# WS2812B-compact.net
KiCad netlist of a schematic drawn in EAGLE
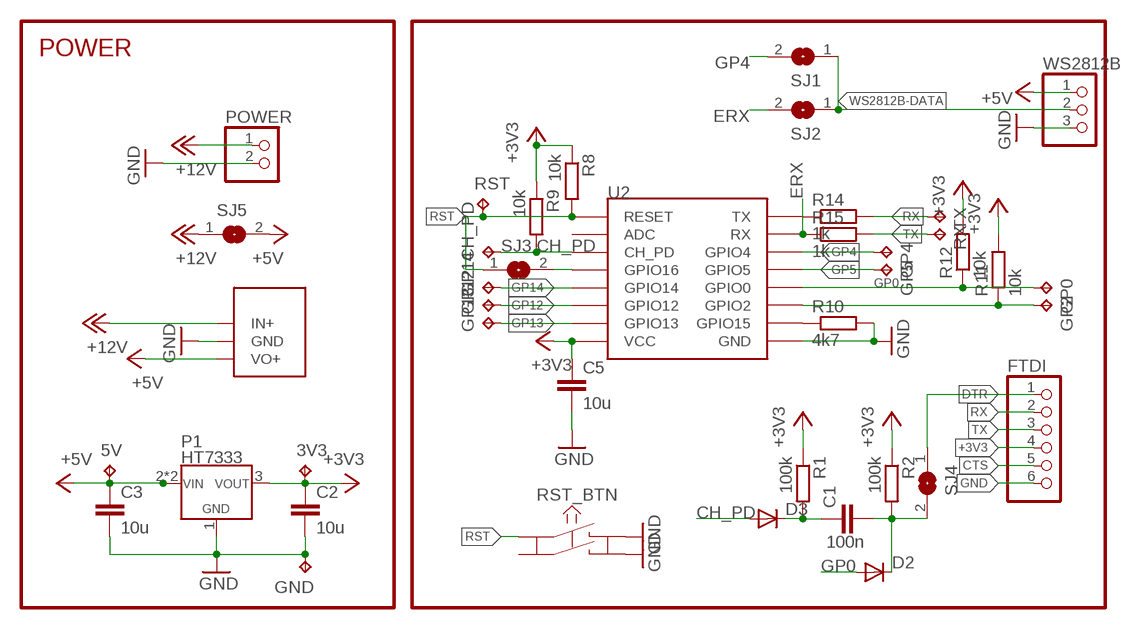
[diagram p0: schematic, sheet 1]

(export (version "E")
  (design (tool "Eeschema 10.0.6"))
  (components
    (comp (ref "3V3")
      (value "TPB2,54")
      (footprint "eagle-import:B2,54")
      (libsource (lib "eagle-import") (part "TPB2,54"))
    )
    (comp (ref "5V")
      (value "TPB2,54")
      (footprint "eagle-import:B2,54")
      (libsource (lib "eagle-import") (part "TPB2,54"))
    )
    (comp (ref "C1")
      (value "100n")
      (footprint "eagle-import:C1206")
      (libsource (lib "eagle-import") (part "C-EUC1206"))
    )
    (comp (ref "C2")
      (value "10u")
      (footprint "eagle-import:C1206")
      (libsource (lib "eagle-import") (part "C-EUC1206"))
    )
    (comp (ref "C3")
      (value "10u")
      (footprint "eagle-import:C1206")
      (libsource (lib "eagle-import") (part "C-EUC1206"))
    )
    (comp (ref "C5")
      (value "10u")
      (footprint "eagle-import:C1206")
      (libsource (lib "eagle-import") (part "C-EUC1206"))
    )
    (comp (ref "CH_PD")
      (value "TPB1,27")
      (footprint "eagle-import:B1,27")
      (libsource (lib "eagle-import") (part "TPB1,27"))
    )
    (comp (ref "D2")
      (value "DIODE-MINIMELF")
      (footprint "eagle-import:MINIMELF")
      (libsource (lib "eagle-import") (part "DIODE-MINIMELF"))
    )
    (comp (ref "D3")
      (value "DIODE-MINIMELF")
      (footprint "eagle-import:MINIMELF")
      (libsource (lib "eagle-import") (part "DIODE-MINIMELF"))
    )
    (comp (ref "FTDI")
      (value "PINHD-1X06_2.54-S")
      (footprint "eagle-import:1X06-S")
      (libsource (lib "eagle-import") (part "PINHD-1X06_2.54-S"))
    )
    (comp (ref "GND")
      (value "TPB2,54")
      (footprint "eagle-import:B2,54")
      (libsource (lib "eagle-import") (part "TPB2,54"))
    )
    (comp (ref "GP0")
      (value "TPB1,27")
      (footprint "eagle-import:B1,27")
      (libsource (lib "eagle-import") (part "TPB1,27"))
    )
    (comp (ref "GP2")
      (value "TPB1,27")
      (footprint "eagle-import:B1,27")
      (libsource (lib "eagle-import") (part "TPB1,27"))
    )
    (comp (ref "GP4")
      (value "TPB1,27")
      (footprint "eagle-import:B1,27")
      (libsource (lib "eagle-import") (part "TPB1,27"))
    )
    (comp (ref "GP5")
      (value "TPB1,27")
      (footprint "eagle-import:B1,27")
      (libsource (lib "eagle-import") (part "TPB1,27"))
    )
    (comp (ref "GP12")
      (value "TPB1,27")
      (footprint "eagle-import:B1,27")
      (libsource (lib "eagle-import") (part "TPB1,27"))
    )
    (comp (ref "GP13")
      (value "TPB1,27")
      (footprint "eagle-import:B1,27")
      (libsource (lib "eagle-import") (part "TPB1,27"))
    )
    (comp (ref "GP14")
      (value "TPB1,27")
      (footprint "eagle-import:B1,27")
      (libsource (lib "eagle-import") (part "TPB1,27"))
    )
    (comp (ref "P1")
      (value "HT7333")
      (footprint "eagle-import:SOT89")
      (libsource (lib "eagle-import") (part "HT7333SOT89"))
    )
    (comp (ref "POWER")
      (value "PINHD-1X2")
      (footprint "eagle-import:1X02")
      (libsource (lib "eagle-import") (part "PINHD-1X2"))
    )
    (comp (ref "R1")
      (value "100k")
      (footprint "eagle-import:R0805")
      (libsource (lib "eagle-import") (part "R-EU_R0805"))
    )
    (comp (ref "R2")
      (value "100k")
      (footprint "eagle-import:R0805")
      (libsource (lib "eagle-import") (part "R-EU_R0805"))
    )
    (comp (ref "R8")
      (value "10k")
      (footprint "eagle-import:R0805")
      (libsource (lib "eagle-import") (part "R-EU_R0805"))
    )
    (comp (ref "R9")
      (value "10k")
      (footprint "eagle-import:R0805")
      (libsource (lib "eagle-import") (part "R-EU_R0805"))
    )
    (comp (ref "R10")
      (value "4k7")
      (footprint "eagle-import:R0805")
      (libsource (lib "eagle-import") (part "R-EU_R0805"))
    )
    (comp (ref "R11")
      (value "10k")
      (footprint "eagle-import:R0805")
      (libsource (lib "eagle-import") (part "R-EU_R0805"))
    )
    (comp (ref "R12")
      (value "10k")
      (footprint "eagle-import:R0805")
      (libsource (lib "eagle-import") (part "R-EU_R0805"))
    )
    (comp (ref "R14")
      (value "1k")
      (footprint "eagle-import:R0805")
      (libsource (lib "eagle-import") (part "R-EU_R0805"))
    )
    (comp (ref "R15")
      (value "1k")
      (footprint "eagle-import:R0805")
      (libsource (lib "eagle-import") (part "R-EU_R0805"))
    )
    (comp (ref "RST")
      (value "TPB1,27")
      (footprint "eagle-import:B1,27")
      (libsource (lib "eagle-import") (part "TPB1,27"))
    )
    (comp (ref "RST_BTN")
      (value "KSM611A")
      (footprint "eagle-import:KSM611A")
      (libsource (lib "eagle-import") (part "KSM611A"))
    )
    (comp (ref "RX")
      (value "TPB1,27")
      (footprint "eagle-import:B1,27")
      (libsource (lib "eagle-import") (part "TPB1,27"))
    )
    (comp (ref "SJ1") (value "SJ") (footprint "eagle-import:SJ") (libsource (lib "eagle-import") (part "SJ")))
    (comp (ref "SJ2") (value "SJ") (footprint "eagle-import:SJ") (libsource (lib "eagle-import") (part "SJ")))
    (comp (ref "SJ3") (value "SJ") (footprint "eagle-import:SJ") (libsource (lib "eagle-import") (part "SJ")))
    (comp (ref "SJ4") (value "SJ") (footprint "eagle-import:SJ") (libsource (lib "eagle-import") (part "SJ")))
    (comp (ref "SJ5") (value "SJ") (footprint "eagle-import:SJ") (libsource (lib "eagle-import") (part "SJ")))
    (comp (ref "TX")
      (value "TPB1,27")
      (footprint "eagle-import:B1,27")
      (libsource (lib "eagle-import") (part "TPB1,27"))
    )
    (comp (ref "U$1")
      (value "BUCK_CONVERTER_TE818_VAR")
      (footprint "eagle-import:BUCK_CONVERTER_TE818_VAR")
      (libsource (lib "eagle-import") (part "BUCK_CONVERTER_TE818_VAR"))
    )
    (comp (ref "U2")
      (value "ESP12SMD")
      (footprint "eagle-import:ESP12-SMD")
      (libsource (lib "eagle-import") (part "ESP12SMD"))
    )
    (comp (ref "WS2812B")
      (value "PINHD-1X03_2.54-S")
      (footprint "eagle-import:1X03-S")
      (libsource (lib "eagle-import") (part "PINHD-1X03_2.54-S"))
    )
  )
  (nets
    (net (code "1") (name "+3V3") (class "Default")
      (node (ref "3V3") (pin "TP") (pinfunction "TP_TP") (pintype "input"))
      (node (ref "C2") (pin "1") (pinfunction "1_1") (pintype "passive"))
      (node (ref "C5") (pin "1") (pinfunction "1_1") (pintype "passive"))
      (node (ref "FTDI") (pin "4") (pinfunction "4_4") (pintype "passive"))
      (node (ref "P1") (pin "3") (pinfunction "VOUT_3") (pintype "power_in"))
      (node (ref "R1") (pin "1") (pinfunction "1_1") (pintype "passive"))
      (node (ref "R11") (pin "2") (pinfunction "2_2") (pintype "passive"))
      (node (ref "R12") (pin "2") (pinfunction "2_2") (pintype "passive"))
      (node (ref "R2") (pin "1") (pinfunction "1_1") (pintype "passive"))
      (node (ref "R8") (pin "1") (pinfunction "1_1") (pintype "passive"))
      (node (ref "R9") (pin "1") (pinfunction "1_1") (pintype "passive"))
      (node (ref "U2") (pin "VCC") (pinfunction "VCC_VCC") (pintype "bidirectional"))
    )
    (net (code "2") (name "+5V") (class "Default")
      (node (ref "5V") (pin "TP") (pinfunction "TP_TP") (pintype "input"))
      (node (ref "C3") (pin "1") (pinfunction "1_1") (pintype "passive"))
      (node (ref "P1") (pin "2") (pinfunction "VIN_2") (pintype "power_in"))
      (node (ref "P1") (pin "2@1") (pinfunction "VIN_2@1") (pintype "power_in"))
      (node (ref "SJ5") (pin "2") (pinfunction "2_2") (pintype "passive"))
      (node (ref "U$1") (pin "VO+") (pinfunction "VO+_VO+") (pintype "bidirectional"))
      (node (ref "WS2812B") (pin "1") (pinfunction "1_1") (pintype "passive"))
    )
    (net (code "3") (name "+12V") (class "Default")
      (node (ref "POWER") (pin "1") (pinfunction "1_1") (pintype "passive"))
      (node (ref "SJ5") (pin "1") (pinfunction "1_1") (pintype "passive"))
      (node (ref "U$1") (pin "IN+") (pinfunction "IN+_IN+") (pintype "bidirectional"))
    )
    (net (code "4") (name "/CH_PD") (class "Default")
      (node (ref "CH_PD") (pin "TP") (pinfunction "TP_TP") (pintype "input"))
      (node (ref "D3") (pin "A") (pinfunction "A_A") (pintype "passive"))
      (node (ref "R9") (pin "2") (pinfunction "2_2") (pintype "passive"))
      (node (ref "U2") (pin "CH_PD") (pinfunction "CH_PD_CH_PD") (pintype "bidirectional"))
    )
    (net (code "5") (name "/ERX") (class "Default")
      (node (ref "R15") (pin "1") (pinfunction "1_1") (pintype "passive"))
      (node (ref "SJ2") (pin "2") (pinfunction "2_2") (pintype "passive"))
      (node (ref "U2") (pin "RXD0") (pinfunction "RX_RXD0") (pintype "bidirectional"))
    )
    (net (code "6") (name "/GP0") (class "Default")
      (node (ref "D2") (pin "A") (pinfunction "A_A") (pintype "passive"))
      (node (ref "GP0") (pin "TP") (pinfunction "TP_TP") (pintype "input"))
      (node (ref "R12") (pin "1") (pinfunction "1_1") (pintype "passive"))
      (node (ref "U2") (pin "GPIO0") (pinfunction "GPIO0_GPIO0") (pintype "bidirectional"))
    )
    (net (code "7") (name "CTS") (class "Default")
      (node (ref "FTDI") (pin "5") (pinfunction "5_5") (pintype "passive"))
    )
    (net (code "8") (name "DTR") (class "Default")
      (node (ref "FTDI") (pin "1") (pinfunction "1_1") (pintype "passive"))
      (node (ref "SJ4") (pin "1") (pinfunction "1_1") (pintype "passive"))
    )
    (net (code "9") (name "GND") (class "Default")
      (node (ref "C2") (pin "2") (pinfunction "2_2") (pintype "passive"))
      (node (ref "C3") (pin "2") (pinfunction "2_2") (pintype "passive"))
      (node (ref "C5") (pin "2") (pinfunction "2_2") (pintype "passive"))
      (node (ref "FTDI") (pin "6") (pinfunction "6_6") (pintype "passive"))
      (node (ref "GND") (pin "TP") (pinfunction "TP_TP") (pintype "input"))
      (node (ref "P1") (pin "1") (pinfunction "GND_1") (pintype "power_in"))
      (node (ref "POWER") (pin "2") (pinfunction "2_2") (pintype "passive"))
      (node (ref "R10") (pin "2") (pinfunction "2_2") (pintype "passive"))
      (node (ref "RST_BTN") (pin "B") (pinfunction "B_B") (pintype "passive"))
      (node (ref "RST_BTN") (pin "D") (pinfunction "D_D") (pintype "passive"))
      (node (ref "U$1") (pin "GND") (pinfunction "GND_GND") (pintype "bidirectional"))
      (node (ref "U2") (pin "GND") (pinfunction "GND_GND") (pintype "bidirectional"))
      (node (ref "WS2812B") (pin "3") (pinfunction "3_3") (pintype "passive"))
    )
    (net (code "10") (name "GP4") (class "Default")
      (node (ref "GP4") (pin "TP") (pinfunction "TP_TP") (pintype "input"))
      (node (ref "SJ1") (pin "2") (pinfunction "2_2") (pintype "passive"))
      (node (ref "U2") (pin "GPIO4") (pinfunction "GPIO4_GPIO4") (pintype "bidirectional"))
    )
    (net (code "11") (name "GP5") (class "Default")
      (node (ref "GP5") (pin "TP") (pinfunction "TP_TP") (pintype "input"))
      (node (ref "U2") (pin "GPIO5") (pinfunction "GPIO5_GPIO5") (pintype "bidirectional"))
    )
    (net (code "12") (name "GP12") (class "Default")
      (node (ref "GP12") (pin "TP") (pinfunction "TP_TP") (pintype "input"))
      (node (ref "U2") (pin "GPIO12") (pinfunction "GPIO12_GPIO12") (pintype "bidirectional"))
    )
    (net (code "13") (name "GP13") (class "Default")
      (node (ref "GP13") (pin "TP") (pinfunction "TP_TP") (pintype "input"))
      (node (ref "U2") (pin "GPIO13") (pinfunction "GPIO13_GPIO13") (pintype "bidirectional"))
    )
    (net (code "14") (name "GP14") (class "Default")
      (node (ref "GP14") (pin "TP") (pinfunction "TP_TP") (pintype "input"))
      (node (ref "U2") (pin "GPIO14") (pinfunction "GPIO14_GPIO14") (pintype "bidirectional"))
    )
    (net (code "15") (name "Net-(C1-Pad1)") (class "Default")
      (node (ref "C1") (pin "1") (pinfunction "1_1") (pintype "passive"))
      (node (ref "D3") (pin "C") (pinfunction "C_C") (pintype "passive"))
      (node (ref "R1") (pin "2") (pinfunction "2_2") (pintype "passive"))
    )
    (net (code "16") (name "Net-(C1-Pad2)") (class "Default")
      (node (ref "C1") (pin "2") (pinfunction "2_2") (pintype "passive"))
      (node (ref "D2") (pin "C") (pinfunction "C_C") (pintype "passive"))
      (node (ref "R2") (pin "2") (pinfunction "2_2") (pintype "passive"))
      (node (ref "SJ4") (pin "2") (pinfunction "2_2") (pintype "passive"))
    )
    (net (code "17") (name "Net-(GP2-PadTP)") (class "Default")
      (node (ref "GP2") (pin "TP") (pinfunction "TP_TP") (pintype "input"))
      (node (ref "R11") (pin "1") (pinfunction "1_1") (pintype "passive"))
      (node (ref "U2") (pin "GPIO2") (pinfunction "GPIO2_GPIO2") (pintype "bidirectional"))
    )
    (net (code "18") (name "Net-(R10-Pad1)") (class "Default")
      (node (ref "R10") (pin "1") (pinfunction "1_1") (pintype "passive"))
      (node (ref "U2") (pin "GPIO15") (pinfunction "GPIO15_GPIO15") (pintype "bidirectional"))
    )
    (net (code "19") (name "Net-(SJ3-Pad2)") (class "Default")
      (node (ref "SJ3") (pin "2") (pinfunction "2_2") (pintype "passive"))
      (node (ref "U2") (pin "GPIO16") (pinfunction "GPIO16_GPIO16") (pintype "bidirectional"))
    )
    (net (code "20") (name "Net-(U2-TX)") (class "Default")
      (node (ref "R14") (pin "1") (pinfunction "1_1") (pintype "passive"))
      (node (ref "U2") (pin "TXD0") (pinfunction "TX_TXD0") (pintype "bidirectional"))
    )
    (net (code "21") (name "RST") (class "Default")
      (node (ref "R8") (pin "2") (pinfunction "2_2") (pintype "passive"))
      (node (ref "RST") (pin "TP") (pinfunction "TP_TP") (pintype "input"))
      (node (ref "RST_BTN") (pin "A") (pinfunction "A_A") (pintype "passive"))
      (node (ref "SJ3") (pin "1") (pinfunction "1_1") (pintype "passive"))
      (node (ref "U2") (pin "RESET") (pinfunction "RESET_RESET") (pintype "bidirectional"))
    )
    (net (code "22") (name "RX") (class "Default")
      (node (ref "FTDI") (pin "2") (pinfunction "2_2") (pintype "passive"))
      (node (ref "R14") (pin "2") (pinfunction "2_2") (pintype "passive"))
      (node (ref "TX") (pin "TP") (pinfunction "TP_TP") (pintype "input"))
    )
    (net (code "23") (name "TX") (class "Default")
      (node (ref "FTDI") (pin "3") (pinfunction "3_3") (pintype "passive"))
      (node (ref "R15") (pin "2") (pinfunction "2_2") (pintype "passive"))
      (node (ref "RX") (pin "TP") (pinfunction "TP_TP") (pintype "input"))
    )
    (net (code "24") (name "WS2812B-DATA") (class "Default")
      (node (ref "SJ1") (pin "1") (pinfunction "1_1") (pintype "passive"))
      (node (ref "SJ2") (pin "1") (pinfunction "1_1") (pintype "passive"))
      (node (ref "WS2812B") (pin "2") (pinfunction "2_2") (pintype "passive"))
    )
    (net (code "25") (name "unconnected-(RST_BTN-PadC)") (class "Default")
      (node (ref "RST_BTN") (pin "C") (pinfunction "C_C") (pintype "passive"))
    )
    (net (code "26") (name "unconnected-(U2-PadADC)") (class "Default")
      (node (ref "U2") (pin "ADC") (pinfunction "ADC_ADC") (pintype "bidirectional"))
    )
  )
)
